# usb-100basefx.net
KiCad netlist of a schematic drawn in EAGLE
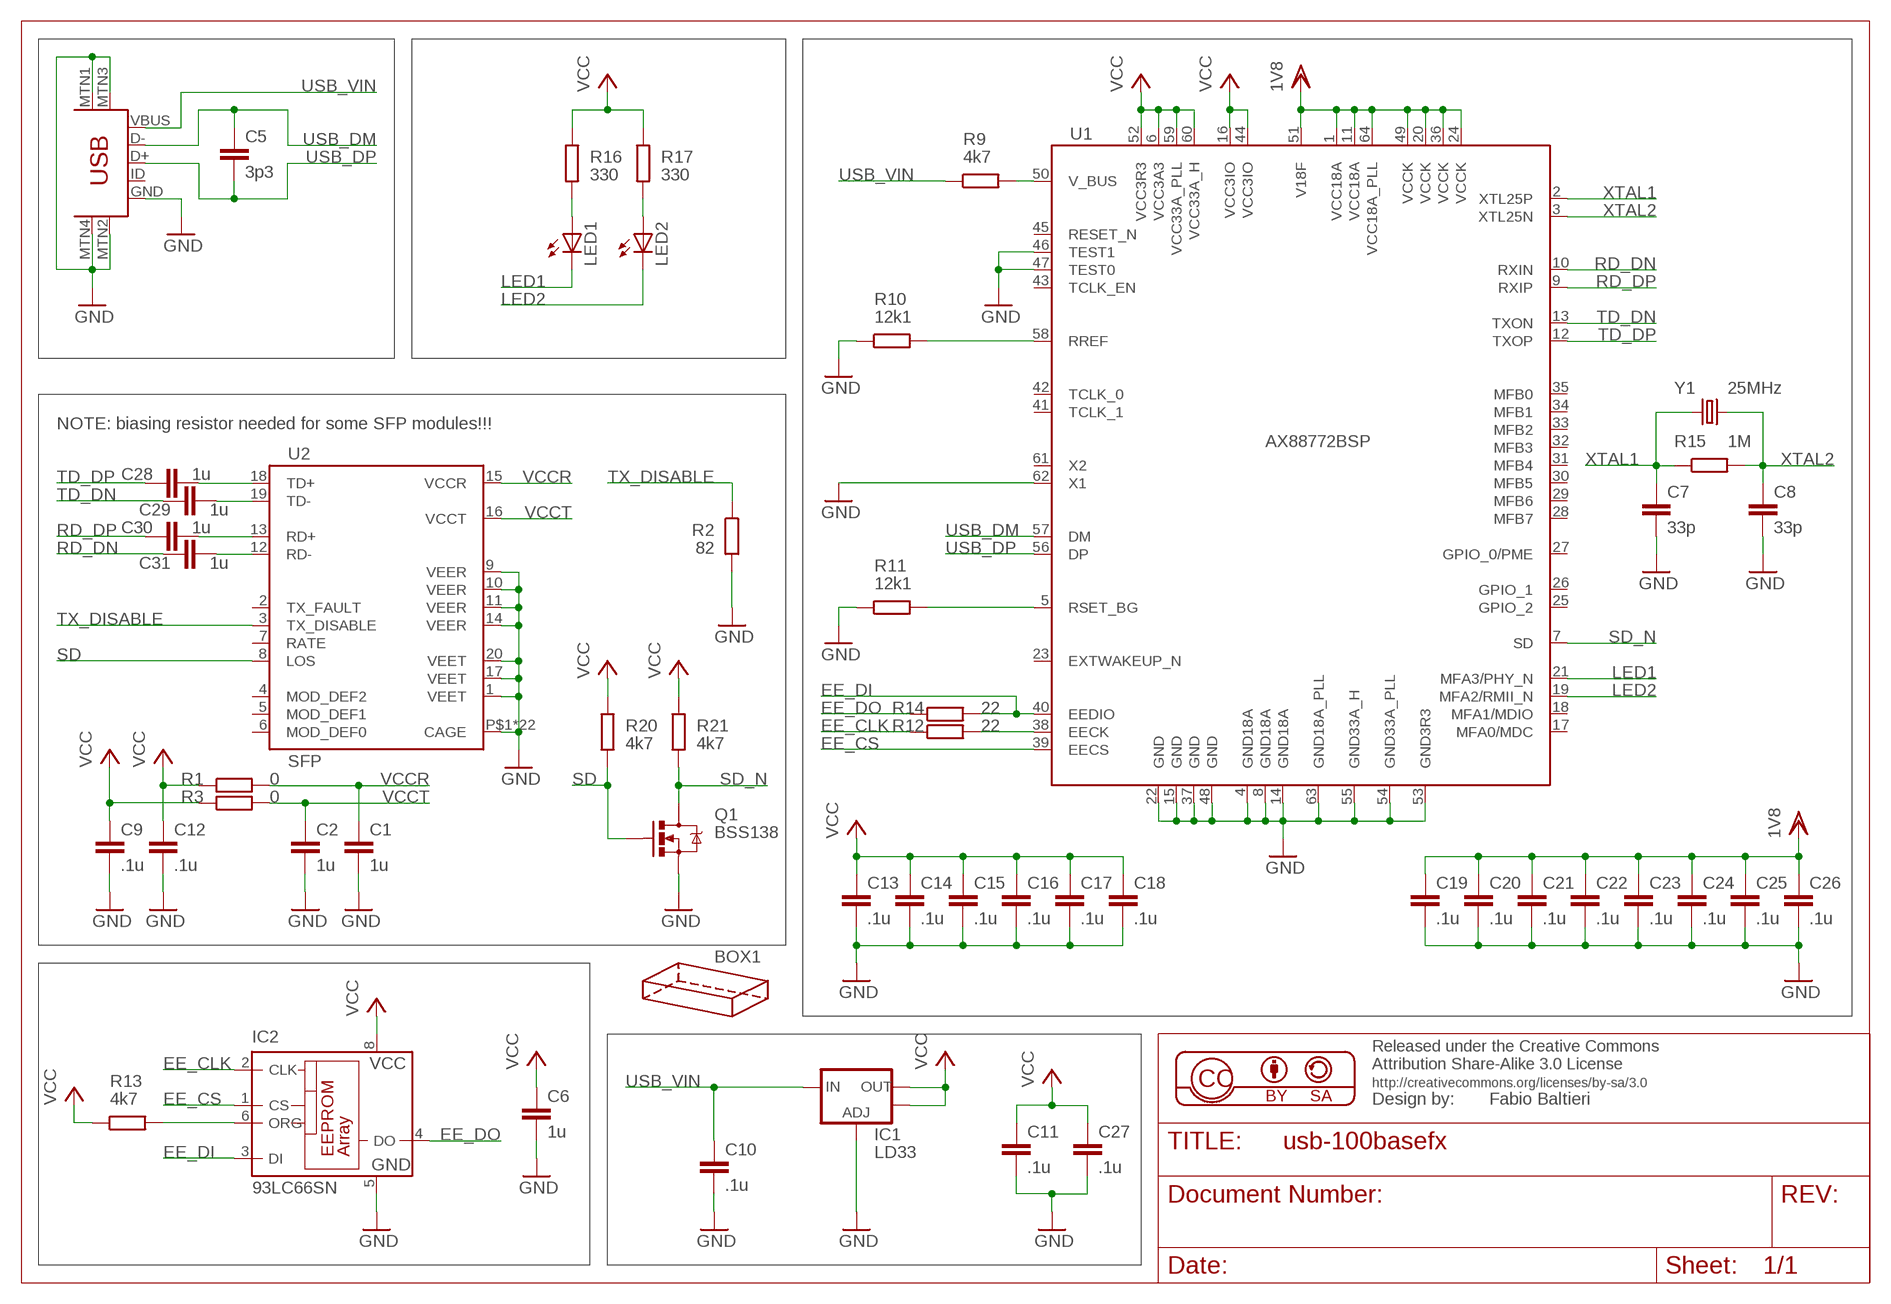
[diagram p0: schematic, sheet 1]

(export (version "E")
  (design (tool "Eeschema 10.0.6"))
  (components
    (comp (ref "BOX1")
      (value "HAMMOND-BOX-H-1H")
      (footprint "eagle-import:1551H-1HOLE")
      (libsource (lib "eagle-import") (part "HAMMOND-BOX-H-1H"))
    )
    (comp (ref "C1")
      (value "1u")
      (footprint "eagle-import:C0603")
      (libsource (lib "eagle-import") (part "C-EUC0603"))
    )
    (comp (ref "C2")
      (value "1u")
      (footprint "eagle-import:C0603")
      (libsource (lib "eagle-import") (part "C-EUC0603"))
    )
    (comp (ref "C5")
      (value "3p3")
      (footprint "eagle-import:C0603")
      (libsource (lib "eagle-import") (part "C-EUC0603"))
    )
    (comp (ref "C6")
      (value "1u")
      (footprint "eagle-import:C0603")
      (libsource (lib "eagle-import") (part "C-EUC0603"))
    )
    (comp (ref "C7")
      (value "33p")
      (footprint "eagle-import:C0603")
      (libsource (lib "eagle-import") (part "C-EUC0603"))
    )
    (comp (ref "C8")
      (value "33p")
      (footprint "eagle-import:C0603")
      (libsource (lib "eagle-import") (part "C-EUC0603"))
    )
    (comp (ref "C9")
      (value ".1u")
      (footprint "eagle-import:C0603")
      (libsource (lib "eagle-import") (part "C-EUC0603"))
    )
    (comp (ref "C10")
      (value ".1u")
      (footprint "eagle-import:C0603")
      (libsource (lib "eagle-import") (part "C-EUC0603"))
    )
    (comp (ref "C11")
      (value ".1u")
      (footprint "eagle-import:C0603")
      (libsource (lib "eagle-import") (part "C-EUC0603"))
    )
    (comp (ref "C12")
      (value ".1u")
      (footprint "eagle-import:C0603")
      (libsource (lib "eagle-import") (part "C-EUC0603"))
    )
    (comp (ref "C13")
      (value ".1u")
      (footprint "eagle-import:C0603")
      (libsource (lib "eagle-import") (part "C-EUC0603"))
    )
    (comp (ref "C14")
      (value ".1u")
      (footprint "eagle-import:C0603")
      (libsource (lib "eagle-import") (part "C-EUC0603"))
    )
    (comp (ref "C15")
      (value ".1u")
      (footprint "eagle-import:C0603")
      (libsource (lib "eagle-import") (part "C-EUC0603"))
    )
    (comp (ref "C16")
      (value ".1u")
      (footprint "eagle-import:C0603")
      (libsource (lib "eagle-import") (part "C-EUC0603"))
    )
    (comp (ref "C17")
      (value ".1u")
      (footprint "eagle-import:C0603")
      (libsource (lib "eagle-import") (part "C-EUC0603"))
    )
    (comp (ref "C18")
      (value ".1u")
      (footprint "eagle-import:C0603")
      (libsource (lib "eagle-import") (part "C-EUC0603"))
    )
    (comp (ref "C19")
      (value ".1u")
      (footprint "eagle-import:C0603")
      (libsource (lib "eagle-import") (part "C-EUC0603"))
    )
    (comp (ref "C20")
      (value ".1u")
      (footprint "eagle-import:C0603")
      (libsource (lib "eagle-import") (part "C-EUC0603"))
    )
    (comp (ref "C21")
      (value ".1u")
      (footprint "eagle-import:C0603")
      (libsource (lib "eagle-import") (part "C-EUC0603"))
    )
    (comp (ref "C22")
      (value ".1u")
      (footprint "eagle-import:C0603")
      (libsource (lib "eagle-import") (part "C-EUC0603"))
    )
    (comp (ref "C23")
      (value ".1u")
      (footprint "eagle-import:C0603")
      (libsource (lib "eagle-import") (part "C-EUC0603"))
    )
    (comp (ref "C24")
      (value ".1u")
      (footprint "eagle-import:C0603")
      (libsource (lib "eagle-import") (part "C-EUC0603"))
    )
    (comp (ref "C25")
      (value ".1u")
      (footprint "eagle-import:C0603")
      (libsource (lib "eagle-import") (part "C-EUC0603"))
    )
    (comp (ref "C26")
      (value ".1u")
      (footprint "eagle-import:C0603")
      (libsource (lib "eagle-import") (part "C-EUC0603"))
    )
    (comp (ref "C27")
      (value ".1u")
      (footprint "eagle-import:C0603")
      (libsource (lib "eagle-import") (part "C-EUC0603"))
    )
    (comp (ref "C28")
      (value "1u")
      (footprint "eagle-import:C0603")
      (libsource (lib "eagle-import") (part "C-EUC0603"))
    )
    (comp (ref "C29")
      (value "1u")
      (footprint "eagle-import:C0603")
      (libsource (lib "eagle-import") (part "C-EUC0603"))
    )
    (comp (ref "C30")
      (value "1u")
      (footprint "eagle-import:C0603")
      (libsource (lib "eagle-import") (part "C-EUC0603"))
    )
    (comp (ref "C31")
      (value "1u")
      (footprint "eagle-import:C0603")
      (libsource (lib "eagle-import") (part "C-EUC0603"))
    )
    (comp (ref "IC1")
      (value "LD33")
      (footprint "eagle-import:SOT223")
      (libsource (lib "eagle-import") (part "V_REG_LM1117SOT223"))
    )
    (comp (ref "IC2")
      (value "93LC66SN")
      (footprint "eagle-import:SO-08")
      (fields (field (name "MF") "MICROCHIP") (field (name "MPN") "93LC66/SN"))
      (libsource (lib "eagle-import") (part "93SNLC66"))
    )
    (comp (ref "LED1")
      (value "LEDCHIPLED_0805")
      (footprint "eagle-import:CHIPLED_0805")
      (libsource (lib "eagle-import") (part "LEDCHIPLED_0805"))
    )
    (comp (ref "LED2")
      (value "LEDCHIPLED_0805")
      (footprint "eagle-import:CHIPLED_0805")
      (libsource (lib "eagle-import") (part "LEDCHIPLED_0805"))
    )
    (comp (ref "Q1")
      (value "BSS138")
      (footprint "eagle-import:SOT23")
      (libsource (lib "eagle-import") (part "MOSFET-NCHANNELBSS123LT1G"))
    )
    (comp (ref "R1")
      (value "0")
      (footprint "eagle-import:R0603")
      (libsource (lib "eagle-import") (part "R-EU_R0603"))
    )
    (comp (ref "R2")
      (value "82")
      (footprint "eagle-import:R0603")
      (libsource (lib "eagle-import") (part "R-EU_R0603"))
    )
    (comp (ref "R3")
      (value "0")
      (footprint "eagle-import:R0603")
      (libsource (lib "eagle-import") (part "R-EU_R0603"))
    )
    (comp (ref "R9")
      (value "4k7")
      (footprint "eagle-import:R0603")
      (libsource (lib "eagle-import") (part "R-EU_R0603"))
    )
    (comp (ref "R10")
      (value "12k1")
      (footprint "eagle-import:R0603")
      (libsource (lib "eagle-import") (part "R-EU_R0603"))
    )
    (comp (ref "R11")
      (value "12k1")
      (footprint "eagle-import:R0603")
      (libsource (lib "eagle-import") (part "R-EU_R0603"))
    )
    (comp (ref "R12")
      (value "22")
      (footprint "eagle-import:R0603")
      (libsource (lib "eagle-import") (part "R-EU_R0603"))
    )
    (comp (ref "R13")
      (value "4k7")
      (footprint "eagle-import:R0603")
      (libsource (lib "eagle-import") (part "R-EU_R0603"))
    )
    (comp (ref "R14")
      (value "22")
      (footprint "eagle-import:R0603")
      (libsource (lib "eagle-import") (part "R-EU_R0603"))
    )
    (comp (ref "R15")
      (value "1M")
      (footprint "eagle-import:R0603")
      (libsource (lib "eagle-import") (part "R-EU_R0603"))
    )
    (comp (ref "R16")
      (value "330")
      (footprint "eagle-import:R0603")
      (libsource (lib "eagle-import") (part "R-EU_R0603"))
    )
    (comp (ref "R17")
      (value "330")
      (footprint "eagle-import:R0603")
      (libsource (lib "eagle-import") (part "R-EU_R0603"))
    )
    (comp (ref "R20")
      (value "4k7")
      (footprint "eagle-import:R0603")
      (libsource (lib "eagle-import") (part "R-EU_R0603"))
    )
    (comp (ref "R21")
      (value "4k7")
      (footprint "eagle-import:R0603")
      (libsource (lib "eagle-import") (part "R-EU_R0603"))
    )
    (comp (ref "U$1")
      (value "USB-MINIB-5PIN")
      (footprint "eagle-import:USB-MINIB")
      (libsource (lib "eagle-import") (part "USB-MINIB-5PIN"))
    )
    (comp (ref "U1")
      (value "AX88772BSP")
      (footprint "eagle-import:LQFP64-0.4MM-SHORTPAD")
      (libsource (lib "eagle-import") (part "AX88772BSP"))
    )
    (comp (ref "U2")
      (value "SFP")
      (footprint "eagle-import:SFP")
      (libsource (lib "eagle-import") (part "SFP"))
    )
    (comp (ref "Y1")
      (value "25MHz")
      (footprint "eagle-import:CRYSTAL-SMD-5X3")
      (libsource (lib "eagle-import") (part "CRYSTAL5X3"))
    )
  )
  (nets
    (net (code "1") (name "/EE_CLK") (class "Default")
      (node (ref "IC2") (pin "2") (pinfunction "CLK_2") (pintype "input"))
      (node (ref "R12") (pin "1") (pinfunction "1_1") (pintype "passive"))
    )
    (net (code "2") (name "/EE_CS") (class "Default")
      (node (ref "IC2") (pin "1") (pinfunction "CS_1") (pintype "input"))
      (node (ref "U1") (pin "39") (pinfunction "EECS_39") (pintype "bidirectional"))
    )
    (net (code "3") (name "/EE_DI") (class "Default")
      (node (ref "IC2") (pin "3") (pinfunction "DI_3") (pintype "input"))
      (node (ref "R14") (pin "2") (pinfunction "2_2") (pintype "passive"))
      (node (ref "U1") (pin "40") (pinfunction "EEDIO_40") (pintype "bidirectional"))
    )
    (net (code "4") (name "/EE_DO") (class "Default")
      (node (ref "IC2") (pin "4") (pinfunction "DO_4") (pintype "tri_state"))
      (node (ref "R14") (pin "1") (pinfunction "1_1") (pintype "passive"))
    )
    (net (code "5") (name "/LED1") (class "Default")
      (node (ref "LED1") (pin "C") (pinfunction "C_C") (pintype "passive"))
      (node (ref "U1") (pin "21") (pinfunction "MFA3/PHY_N_21") (pintype "bidirectional"))
    )
    (net (code "6") (name "/LED2") (class "Default")
      (node (ref "LED2") (pin "C") (pinfunction "C_C") (pintype "passive"))
      (node (ref "U1") (pin "19") (pinfunction "MFA2/RMII_N_19") (pintype "bidirectional"))
    )
    (net (code "7") (name "/RD_DN") (class "Default")
      (node (ref "C31") (pin "1") (pinfunction "1_1") (pintype "passive"))
      (node (ref "U1") (pin "10") (pinfunction "RXIN_10") (pintype "bidirectional"))
    )
    (net (code "8") (name "/RD_DP") (class "Default")
      (node (ref "C30") (pin "1") (pinfunction "1_1") (pintype "passive"))
      (node (ref "U1") (pin "9") (pinfunction "RXIP_9") (pintype "bidirectional"))
    )
    (net (code "9") (name "/SD") (class "Default")
      (node (ref "Q1") (pin "1") (pinfunction "G_1") (pintype "passive"))
      (node (ref "R20") (pin "2") (pinfunction "2_2") (pintype "passive"))
      (node (ref "U2") (pin "8") (pinfunction "LOS_8") (pintype "bidirectional"))
    )
    (net (code "10") (name "/SD_N") (class "Default")
      (node (ref "Q1") (pin "3") (pinfunction "D_3") (pintype "passive"))
      (node (ref "R21") (pin "2") (pinfunction "2_2") (pintype "passive"))
      (node (ref "U1") (pin "7") (pinfunction "SD_7") (pintype "bidirectional"))
    )
    (net (code "11") (name "/TD_DN") (class "Default")
      (node (ref "C29") (pin "1") (pinfunction "1_1") (pintype "passive"))
      (node (ref "U1") (pin "13") (pinfunction "TXON_13") (pintype "bidirectional"))
    )
    (net (code "12") (name "/TD_DP") (class "Default")
      (node (ref "C28") (pin "1") (pinfunction "1_1") (pintype "passive"))
      (node (ref "U1") (pin "12") (pinfunction "TXOP_12") (pintype "bidirectional"))
    )
    (net (code "13") (name "/TX_DISABLE") (class "Default")
      (node (ref "R2") (pin "1") (pinfunction "1_1") (pintype "passive"))
      (node (ref "U2") (pin "3") (pinfunction "TX_DISABLE_3") (pintype "bidirectional"))
    )
    (net (code "14") (name "/USB_DM") (class "Default")
      (node (ref "C5") (pin "1") (pinfunction "1_1") (pintype "passive"))
      (node (ref "U$1") (pin "D-") (pinfunction "D-_D-") (pintype "bidirectional"))
      (node (ref "U1") (pin "57") (pinfunction "DM_57") (pintype "bidirectional"))
    )
    (net (code "15") (name "/USB_DP") (class "Default")
      (node (ref "C5") (pin "2") (pinfunction "2_2") (pintype "passive"))
      (node (ref "U$1") (pin "D+") (pinfunction "D+_D+") (pintype "bidirectional"))
      (node (ref "U1") (pin "56") (pinfunction "DP_56") (pintype "bidirectional"))
    )
    (net (code "16") (name "/USB_VIN") (class "Default")
      (node (ref "C10") (pin "1") (pinfunction "1_1") (pintype "passive"))
      (node (ref "IC1") (pin "3") (pinfunction "IN_3") (pintype "input"))
      (node (ref "R9") (pin "1") (pinfunction "1_1") (pintype "passive"))
      (node (ref "U$1") (pin "VBUS") (pinfunction "VBUS_VBUS") (pintype "bidirectional"))
    )
    (net (code "17") (name "/VCCR") (class "Default")
      (node (ref "C1") (pin "1") (pinfunction "1_1") (pintype "passive"))
      (node (ref "R1") (pin "2") (pinfunction "2_2") (pintype "passive"))
      (node (ref "U2") (pin "15") (pinfunction "VCCR_15") (pintype "bidirectional"))
    )
    (net (code "18") (name "/VCCT") (class "Default")
      (node (ref "C2") (pin "1") (pinfunction "1_1") (pintype "passive"))
      (node (ref "R3") (pin "2") (pinfunction "2_2") (pintype "passive"))
      (node (ref "U2") (pin "16") (pinfunction "VCCT_16") (pintype "bidirectional"))
    )
    (net (code "19") (name "/XTAL1") (class "Default")
      (node (ref "C7") (pin "1") (pinfunction "1_1") (pintype "passive"))
      (node (ref "R15") (pin "1") (pinfunction "1_1") (pintype "passive"))
      (node (ref "U1") (pin "2") (pinfunction "XTL25P_2") (pintype "bidirectional"))
      (node (ref "Y1") (pin "1") (pinfunction "1_1") (pintype "passive"))
    )
    (net (code "20") (name "/XTAL2") (class "Default")
      (node (ref "C8") (pin "1") (pinfunction "1_1") (pintype "passive"))
      (node (ref "R15") (pin "2") (pinfunction "2_2") (pintype "passive"))
      (node (ref "U1") (pin "3") (pinfunction "XTL25N_3") (pintype "bidirectional"))
      (node (ref "Y1") (pin "3") (pinfunction "2_3") (pintype "passive"))
    )
    (net (code "21") (name "1V8") (class "Default")
      (node (ref "C19") (pin "1") (pinfunction "1_1") (pintype "passive"))
      (node (ref "C20") (pin "1") (pinfunction "1_1") (pintype "passive"))
      (node (ref "C21") (pin "1") (pinfunction "1_1") (pintype "passive"))
      (node (ref "C22") (pin "1") (pinfunction "1_1") (pintype "passive"))
      (node (ref "C23") (pin "1") (pinfunction "1_1") (pintype "passive"))
      (node (ref "C24") (pin "1") (pinfunction "1_1") (pintype "passive"))
      (node (ref "C25") (pin "1") (pinfunction "1_1") (pintype "passive"))
      (node (ref "C26") (pin "1") (pinfunction "1_1") (pintype "passive"))
      (node (ref "U1") (pin "1") (pinfunction "VCC18A_1") (pintype "bidirectional"))
      (node (ref "U1") (pin "11") (pinfunction "VCC18A_11") (pintype "bidirectional"))
      (node (ref "U1") (pin "20") (pinfunction "VCCK_20") (pintype "bidirectional"))
      (node (ref "U1") (pin "24") (pinfunction "VCCK_24") (pintype "bidirectional"))
      (node (ref "U1") (pin "36") (pinfunction "VCCK_36") (pintype "bidirectional"))
      (node (ref "U1") (pin "49") (pinfunction "VCCK_49") (pintype "bidirectional"))
      (node (ref "U1") (pin "51") (pinfunction "V18F_51") (pintype "bidirectional"))
      (node (ref "U1") (pin "64") (pinfunction "VCC18A_PLL_64") (pintype "bidirectional"))
    )
    (net (code "22") (name "GND") (class "Default")
      (node (ref "C1") (pin "2") (pinfunction "2_2") (pintype "passive"))
      (node (ref "C10") (pin "2") (pinfunction "2_2") (pintype "passive"))
      (node (ref "C11") (pin "2") (pinfunction "2_2") (pintype "passive"))
      (node (ref "C12") (pin "2") (pinfunction "2_2") (pintype "passive"))
      (node (ref "C13") (pin "2") (pinfunction "2_2") (pintype "passive"))
      (node (ref "C14") (pin "2") (pinfunction "2_2") (pintype "passive"))
      (node (ref "C15") (pin "2") (pinfunction "2_2") (pintype "passive"))
      (node (ref "C16") (pin "2") (pinfunction "2_2") (pintype "passive"))
      (node (ref "C17") (pin "2") (pinfunction "2_2") (pintype "passive"))
      (node (ref "C18") (pin "2") (pinfunction "2_2") (pintype "passive"))
      (node (ref "C19") (pin "2") (pinfunction "2_2") (pintype "passive"))
      (node (ref "C2") (pin "2") (pinfunction "2_2") (pintype "passive"))
      (node (ref "C20") (pin "2") (pinfunction "2_2") (pintype "passive"))
      (node (ref "C21") (pin "2") (pinfunction "2_2") (pintype "passive"))
      (node (ref "C22") (pin "2") (pinfunction "2_2") (pintype "passive"))
      (node (ref "C23") (pin "2") (pinfunction "2_2") (pintype "passive"))
      (node (ref "C24") (pin "2") (pinfunction "2_2") (pintype "passive"))
      (node (ref "C25") (pin "2") (pinfunction "2_2") (pintype "passive"))
      (node (ref "C26") (pin "2") (pinfunction "2_2") (pintype "passive"))
      (node (ref "C27") (pin "2") (pinfunction "2_2") (pintype "passive"))
      (node (ref "C6") (pin "2") (pinfunction "2_2") (pintype "passive"))
      (node (ref "C7") (pin "2") (pinfunction "2_2") (pintype "passive"))
      (node (ref "C8") (pin "2") (pinfunction "2_2") (pintype "passive"))
      (node (ref "C9") (pin "2") (pinfunction "2_2") (pintype "passive"))
      (node (ref "IC1") (pin "1") (pinfunction "ADJ_1") (pintype "input"))
      (node (ref "IC2") (pin "5") (pinfunction "GND_5") (pintype "power_in"))
      (node (ref "Q1") (pin "2") (pinfunction "S_2") (pintype "passive"))
      (node (ref "R10") (pin "1") (pinfunction "1_1") (pintype "passive"))
      (node (ref "R11") (pin "1") (pinfunction "1_1") (pintype "passive"))
      (node (ref "R2") (pin "2") (pinfunction "2_2") (pintype "passive"))
      (node (ref "U$1") (pin "GND") (pinfunction "GND_GND") (pintype "bidirectional"))
      (node (ref "U$1") (pin "MTN1") (pinfunction "MTN2_MTN1") (pintype "bidirectional"))
      (node (ref "U$1") (pin "MTN2") (pinfunction "MTN3_MTN2") (pintype "bidirectional"))
      (node (ref "U$1") (pin "MTN3") (pinfunction "MTN1_MTN3") (pintype "bidirectional"))
      (node (ref "U$1") (pin "MTN4") (pinfunction "MTN4_MTN4") (pintype "bidirectional"))
      (node (ref "U1") (pin "14") (pinfunction "GND18A_14") (pintype "bidirectional"))
      (node (ref "U1") (pin "15") (pinfunction "GND_15") (pintype "bidirectional"))
      (node (ref "U1") (pin "22") (pinfunction "GND_22") (pintype "bidirectional"))
      (node (ref "U1") (pin "37") (pinfunction "GND_37") (pintype "bidirectional"))
      (node (ref "U1") (pin "4") (pinfunction "GND18A_4") (pintype "bidirectional"))
      (node (ref "U1") (pin "46") (pinfunction "TEST1_46") (pintype "bidirectional"))
      (node (ref "U1") (pin "47") (pinfunction "TEST0_47") (pintype "bidirectional"))
      (node (ref "U1") (pin "48") (pinfunction "GND_48") (pintype "bidirectional"))
      (node (ref "U1") (pin "53") (pinfunction "GND3R3_53") (pintype "bidirectional"))
      (node (ref "U1") (pin "54") (pinfunction "GND33A_PLL_54") (pintype "bidirectional"))
      (node (ref "U1") (pin "55") (pinfunction "GND33A_H_55") (pintype "bidirectional"))
      (node (ref "U1") (pin "62") (pinfunction "X1_62") (pintype "bidirectional"))
      (node (ref "U1") (pin "63") (pinfunction "GND18A_PLL_63") (pintype "bidirectional"))
      (node (ref "U1") (pin "8") (pinfunction "GND18A_8") (pintype "bidirectional"))
      (node (ref "U2") (pin "1") (pinfunction "VEET_1") (pintype "bidirectional"))
      (node (ref "U2") (pin "10") (pinfunction "VEER_10") (pintype "bidirectional"))
      (node (ref "U2") (pin "11") (pinfunction "VEER_11") (pintype "bidirectional"))
      (node (ref "U2") (pin "14") (pinfunction "VEER_14") (pintype "bidirectional"))
      (node (ref "U2") (pin "17") (pinfunction "VEET_17") (pintype "bidirectional"))
      (node (ref "U2") (pin "20") (pinfunction "VEET_20") (pintype "bidirectional"))
      (node (ref "U2") (pin "9") (pinfunction "VEER_9") (pintype "bidirectional"))
      (node (ref "U2") (pin "P$1") (pinfunction "CAGE_P$1") (pintype "bidirectional"))
      (node (ref "U2") (pin "P$10") (pinfunction "CAGE_P$10") (pintype "bidirectional"))
      (node (ref "U2") (pin "P$11") (pinfunction "CAGE_P$11") (pintype "bidirectional"))
      (node (ref "U2") (pin "P$12") (pinfunction "CAGE_P$12") (pintype "bidirectional"))
      (node (ref "U2") (pin "P$13") (pinfunction "CAGE_P$13") (pintype "bidirectional"))
      (node (ref "U2") (pin "P$14") (pinfunction "CAGE_P$14") (pintype "bidirectional"))
      (node (ref "U2") (pin "P$15") (pinfunction "CAGE_P$15") (pintype "bidirectional"))
      (node (ref "U2") (pin "P$16") (pinfunction "CAGE_P$16") (pintype "bidirectional"))
      (node (ref "U2") (pin "P$17") (pinfunction "CAGE_P$17") (pintype "bidirectional"))
      (node (ref "U2") (pin "P$18") (pinfunction "CAGE_P$18") (pintype "bidirectional"))
      (node (ref "U2") (pin "P$19") (pinfunction "CAGE_P$19") (pintype "bidirectional"))
      (node (ref "U2") (pin "P$2") (pinfunction "CAGE_P$2") (pintype "bidirectional"))
      (node (ref "U2") (pin "P$20") (pinfunction "CAGE_P$20") (pintype "bidirectional"))
      (node (ref "U2") (pin "P$21") (pinfunction "CAGE_P$21") (pintype "bidirectional"))
      (node (ref "U2") (pin "P$22") (pinfunction "CAGE_P$22") (pintype "bidirectional"))
      (node (ref "U2") (pin "P$3") (pinfunction "CAGE_P$3") (pintype "bidirectional"))
      (node (ref "U2") (pin "P$4") (pinfunction "CAGE_P$4") (pintype "bidirectional"))
      (node (ref "U2") (pin "P$5") (pinfunction "CAGE_P$5") (pintype "bidirectional"))
      (node (ref "U2") (pin "P$6") (pinfunction "CAGE_P$6") (pintype "bidirectional"))
      (node (ref "U2") (pin "P$7") (pinfunction "CAGE_P$7") (pintype "bidirectional"))
      (node (ref "U2") (pin "P$8") (pinfunction "CAGE_P$8") (pintype "bidirectional"))
      (node (ref "U2") (pin "P$9") (pinfunction "CAGE_P$9") (pintype "bidirectional"))
    )
    (net (code "23") (name "Net-(IC2-ORG)") (class "Default")
      (node (ref "IC2") (pin "6") (pinfunction "ORG_6") (pintype "input"))
      (node (ref "R13") (pin "2") (pinfunction "2_2") (pintype "passive"))
    )
    (net (code "24") (name "Net-(LED1-PadA)") (class "Default")
      (node (ref "LED1") (pin "A") (pinfunction "A_A") (pintype "passive"))
      (node (ref "R16") (pin "2") (pinfunction "2_2") (pintype "passive"))
    )
    (net (code "25") (name "Net-(LED2-PadA)") (class "Default")
      (node (ref "LED2") (pin "A") (pinfunction "A_A") (pintype "passive"))
      (node (ref "R17") (pin "2") (pinfunction "2_2") (pintype "passive"))
    )
    (net (code "26") (name "Net-(U1-EECK)") (class "Default")
      (node (ref "R12") (pin "2") (pinfunction "2_2") (pintype "passive"))
      (node (ref "U1") (pin "38") (pinfunction "EECK_38") (pintype "bidirectional"))
    )
    (net (code "27") (name "Net-(U1-RREF)") (class "Default")
      (node (ref "R10") (pin "2") (pinfunction "2_2") (pintype "passive"))
      (node (ref "U1") (pin "58") (pinfunction "RREF_58") (pintype "bidirectional"))
    )
    (net (code "28") (name "Net-(U1-RSET_BG)") (class "Default")
      (node (ref "R11") (pin "2") (pinfunction "2_2") (pintype "passive"))
      (node (ref "U1") (pin "5") (pinfunction "RSET_BG_5") (pintype "bidirectional"))
    )
    (net (code "29") (name "Net-(U1-V_BUS)") (class "Default")
      (node (ref "R9") (pin "2") (pinfunction "2_2") (pintype "passive"))
      (node (ref "U1") (pin "50") (pinfunction "V_BUS_50") (pintype "bidirectional"))
    )
    (net (code "30") (name "Net-(U2-RD+)") (class "Default")
      (node (ref "C30") (pin "2") (pinfunction "2_2") (pintype "passive"))
      (node (ref "U2") (pin "13") (pinfunction "RD+_13") (pintype "bidirectional"))
    )
    (net (code "31") (name "Net-(U2-RD-)") (class "Default")
      (node (ref "C31") (pin "2") (pinfunction "2_2") (pintype "passive"))
      (node (ref "U2") (pin "12") (pinfunction "RD-_12") (pintype "bidirectional"))
    )
    (net (code "32") (name "Net-(U2-TD+)") (class "Default")
      (node (ref "C28") (pin "2") (pinfunction "2_2") (pintype "passive"))
      (node (ref "U2") (pin "18") (pinfunction "TD+_18") (pintype "bidirectional"))
    )
    (net (code "33") (name "Net-(U2-TD-)") (class "Default")
      (node (ref "C29") (pin "2") (pinfunction "2_2") (pintype "passive"))
      (node (ref "U2") (pin "19") (pinfunction "TD-_19") (pintype "bidirectional"))
    )
    (net (code "34") (name "VCC") (class "Default")
      (node (ref "C11") (pin "1") (pinfunction "1_1") (pintype "passive"))
      (node (ref "C12") (pin "1") (pinfunction "1_1") (pintype "passive"))
      (node (ref "C13") (pin "1") (pinfunction "1_1") (pintype "passive"))
      (node (ref "C14") (pin "1") (pinfunction "1_1") (pintype "passive"))
      (node (ref "C15") (pin "1") (pinfunction "1_1") (pintype "passive"))
      (node (ref "C16") (pin "1") (pinfunction "1_1") (pintype "passive"))
      (node (ref "C17") (pin "1") (pinfunction "1_1") (pintype "passive"))
      (node (ref "C18") (pin "1") (pinfunction "1_1") (pintype "passive"))
      (node (ref "C27") (pin "1") (pinfunction "1_1") (pintype "passive"))
      (node (ref "C6") (pin "1") (pinfunction "1_1") (pintype "passive"))
      (node (ref "C9") (pin "1") (pinfunction "1_1") (pintype "passive"))
      (node (ref "IC1") (pin "2") (pinfunction "OUT_2") (pintype "output"))
      (node (ref "IC1") (pin "4") (pinfunction "OUT_4") (pintype "output"))
      (node (ref "IC2") (pin "8") (pinfunction "VCC_8") (pintype "power_in"))
      (node (ref "R1") (pin "1") (pinfunction "1_1") (pintype "passive"))
      (node (ref "R13") (pin "1") (pinfunction "1_1") (pintype "passive"))
      (node (ref "R16") (pin "1") (pinfunction "1_1") (pintype "passive"))
      (node (ref "R17") (pin "1") (pinfunction "1_1") (pintype "passive"))
      (node (ref "R20") (pin "1") (pinfunction "1_1") (pintype "passive"))
      (node (ref "R21") (pin "1") (pinfunction "1_1") (pintype "passive"))
      (node (ref "R3") (pin "1") (pinfunction "1_1") (pintype "passive"))
      (node (ref "U1") (pin "16") (pinfunction "VCC3IO_16") (pintype "bidirectional"))
      (node (ref "U1") (pin "44") (pinfunction "VCC3IO_44") (pintype "bidirectional"))
      (node (ref "U1") (pin "52") (pinfunction "VCC3R3_52") (pintype "bidirectional"))
      (node (ref "U1") (pin "59") (pinfunction "VCC33A_PLL_59") (pintype "bidirectional"))
      (node (ref "U1") (pin "6") (pinfunction "VCC3A3_6") (pintype "bidirectional"))
      (node (ref "U1") (pin "60") (pinfunction "VCC33A_H_60") (pintype "bidirectional"))
    )
    (net (code "35") (name "unconnected-(IC2-NU-Pad7)") (class "Default")
      (node (ref "IC2") (pin "7") (pinfunction "NU_7") (pintype "passive"))
    )
    (net (code "36") (name "unconnected-(U$1-PadID)") (class "Default")
      (node (ref "U$1") (pin "ID") (pinfunction "ID_ID") (pintype "bidirectional"))
    )
    (net (code "37") (name "unconnected-(U1-EXTWAKEUP_N-Pad23)") (class "Default")
      (node (ref "U1") (pin "23") (pinfunction "EXTWAKEUP_N_23") (pintype "bidirectional"))
    )
    (net (code "38") (name "unconnected-(U1-GPIO_0{slash}PME-Pad27)") (class "Default")
      (node (ref "U1") (pin "27") (pinfunction "GPIO_0/PME_27") (pintype "bidirectional"))
    )
    (net (code "39") (name "unconnected-(U1-GPIO_1-Pad26)") (class "Default")
      (node (ref "U1") (pin "26") (pinfunction "GPIO_1_26") (pintype "bidirectional"))
    )
    (net (code "40") (name "unconnected-(U1-GPIO_2-Pad25)") (class "Default")
      (node (ref "U1") (pin "25") (pinfunction "GPIO_2_25") (pintype "bidirectional"))
    )
    (net (code "41") (name "unconnected-(U1-MFA0{slash}MDC-Pad17)") (class "Default")
      (node (ref "U1") (pin "17") (pinfunction "MFA0/MDC_17") (pintype "bidirectional"))
    )
    (net (code "42") (name "unconnected-(U1-MFA1{slash}MDIO-Pad18)") (class "Default")
      (node (ref "U1") (pin "18") (pinfunction "MFA1/MDIO_18") (pintype "bidirectional"))
    )
    (net (code "43") (name "unconnected-(U1-MFB0-Pad35)") (class "Default")
      (node (ref "U1") (pin "35") (pinfunction "MFB0_35") (pintype "bidirectional"))
    )
    (net (code "44") (name "unconnected-(U1-MFB1-Pad34)") (class "Default")
      (node (ref "U1") (pin "34") (pinfunction "MFB1_34") (pintype "bidirectional"))
    )
    (net (code "45") (name "unconnected-(U1-MFB2-Pad33)") (class "Default")
      (node (ref "U1") (pin "33") (pinfunction "MFB2_33") (pintype "bidirectional"))
    )
    (net (code "46") (name "unconnected-(U1-MFB3-Pad32)") (class "Default")
      (node (ref "U1") (pin "32") (pinfunction "MFB3_32") (pintype "bidirectional"))
    )
    (net (code "47") (name "unconnected-(U1-MFB4-Pad31)") (class "Default")
      (node (ref "U1") (pin "31") (pinfunction "MFB4_31") (pintype "bidirectional"))
    )
    (net (code "48") (name "unconnected-(U1-MFB5-Pad30)") (class "Default")
      (node (ref "U1") (pin "30") (pinfunction "MFB5_30") (pintype "bidirectional"))
    )
    (net (code "49") (name "unconnected-(U1-MFB6-Pad29)") (class "Default")
      (node (ref "U1") (pin "29") (pinfunction "MFB6_29") (pintype "bidirectional"))
    )
    (net (code "50") (name "unconnected-(U1-MFB7-Pad28)") (class "Default")
      (node (ref "U1") (pin "28") (pinfunction "MFB7_28") (pintype "bidirectional"))
    )
    (net (code "51") (name "unconnected-(U1-RESET_N-Pad45)") (class "Default")
      (node (ref "U1") (pin "45") (pinfunction "RESET_N_45") (pintype "bidirectional"))
    )
    (net (code "52") (name "unconnected-(U1-TCLK_0-Pad42)") (class "Default")
      (node (ref "U1") (pin "42") (pinfunction "TCLK_0_42") (pintype "bidirectional"))
    )
    (net (code "53") (name "unconnected-(U1-TCLK_1-Pad41)") (class "Default")
      (node (ref "U1") (pin "41") (pinfunction "TCLK_1_41") (pintype "bidirectional"))
    )
    (net (code "54") (name "unconnected-(U1-TCLK_EN-Pad43)") (class "Default")
      (node (ref "U1") (pin "43") (pinfunction "TCLK_EN_43") (pintype "bidirectional"))
    )
    (net (code "55") (name "unconnected-(U1-X2-Pad61)") (class "Default")
      (node (ref "U1") (pin "61") (pinfunction "X2_61") (pintype "bidirectional"))
    )
    (net (code "56") (name "unconnected-(U2-MOD_DEF0-Pad6)") (class "Default")
      (node (ref "U2") (pin "6") (pinfunction "MOD_DEF0_6") (pintype "bidirectional"))
    )
    (net (code "57") (name "unconnected-(U2-MOD_DEF1-Pad5)") (class "Default")
      (node (ref "U2") (pin "5") (pinfunction "MOD_DEF1_5") (pintype "bidirectional"))
    )
    (net (code "58") (name "unconnected-(U2-MOD_DEF2-Pad4)") (class "Default")
      (node (ref "U2") (pin "4") (pinfunction "MOD_DEF2_4") (pintype "bidirectional"))
    )
    (net (code "59") (name "unconnected-(U2-RATE-Pad7)") (class "Default")
      (node (ref "U2") (pin "7") (pinfunction "RATE_7") (pintype "bidirectional"))
    )
    (net (code "60") (name "unconnected-(U2-TX_FAULT-Pad2)") (class "Default")
      (node (ref "U2") (pin "2") (pinfunction "TX_FAULT_2") (pintype "bidirectional"))
    )
  )
)
